# 28DIP.net
KiCad netlist of a schematic drawn in EAGLE
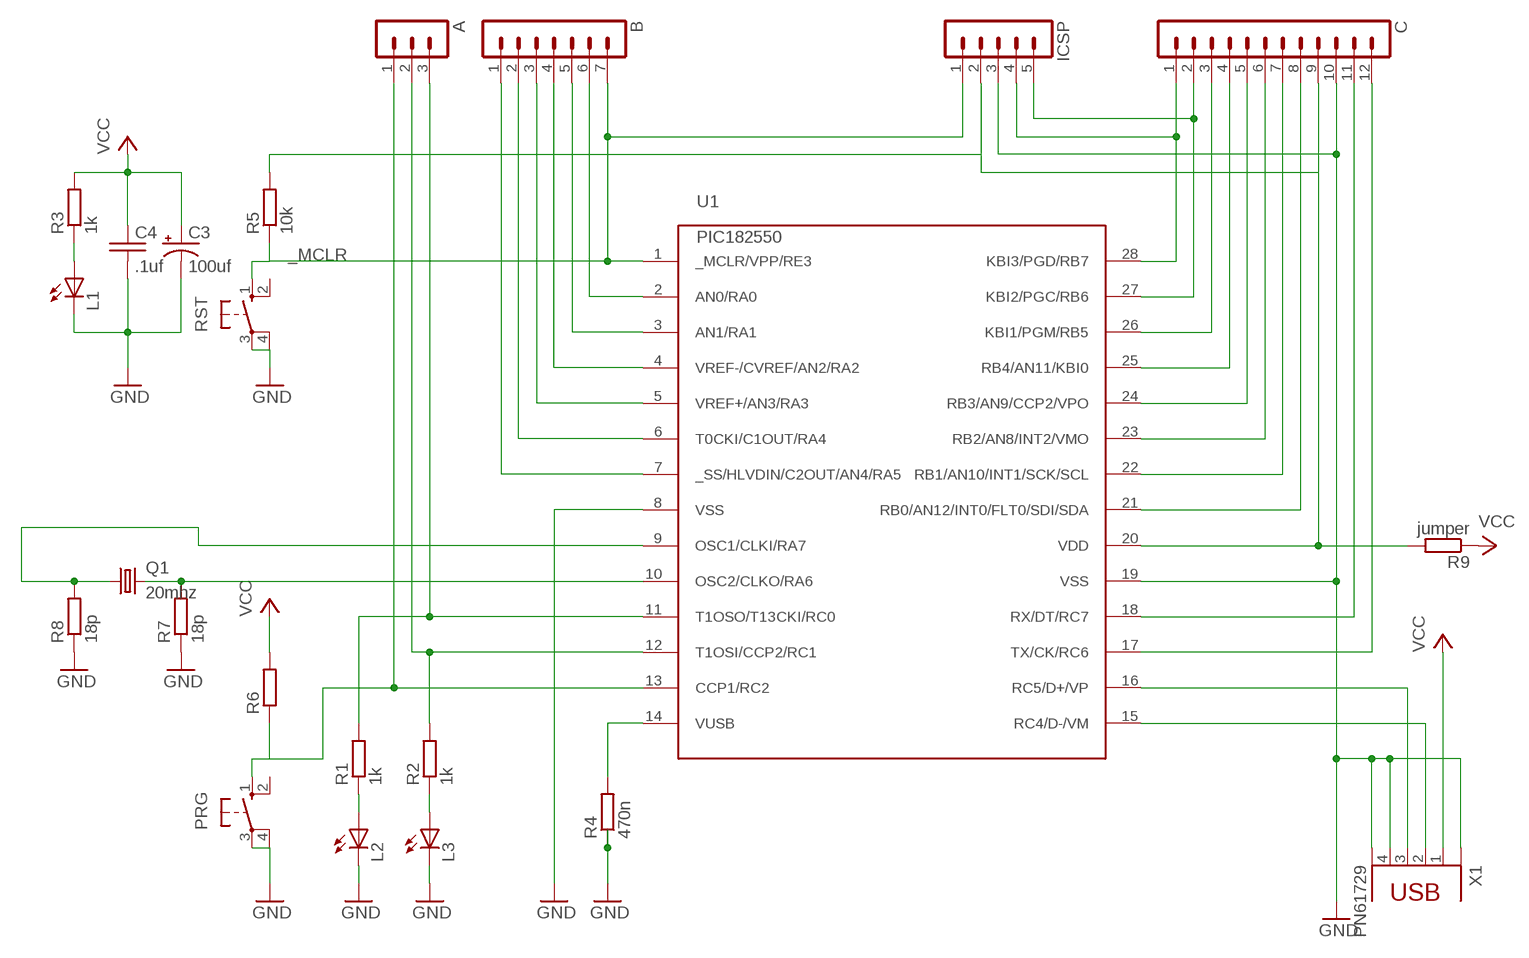
[diagram p0: schematic, sheet 1]

(export (version "E")
  (design (tool "Eeschema 10.0.6"))
  (components
    (comp (ref "A")
      (value "MA03-1")
      (footprint "eagle-import:MA03-1")
      (libsource (lib "eagle-import") (part "MA03-1"))
    )
    (comp (ref "B")
      (value "MA07-1")
      (footprint "eagle-import:MA07-1")
      (libsource (lib "eagle-import") (part "MA07-1"))
    )
    (comp (ref "C")
      (value "MA12-1")
      (footprint "eagle-import:MA12-1")
      (libsource (lib "eagle-import") (part "MA12-1"))
    )
    (comp (ref "C3")
      (value "100uf")
      (footprint "eagle-import:CAP_0200ELECTROLYTIC_0250")
      (libsource (lib "eagle-import") (part "CAP_ELECTROLYTICCAP_0200ELECTROLYTIC_0250"))
    )
    (comp (ref "C4")
      (value ".1uf")
      (footprint "eagle-import:CAP_0100")
      (libsource (lib "eagle-import") (part "CAPCAP_0100"))
    )
    (comp (ref "ICSP")
      (value "MA05-1")
      (footprint "eagle-import:MA05-1")
      (libsource (lib "eagle-import") (part "MA05-1"))
    )
    (comp (ref "L1")
      (value "LED")
      (footprint "eagle-import:LED5MM")
      (libsource (lib "eagle-import") (part "LED"))
    )
    (comp (ref "L2")
      (value "LED")
      (footprint "eagle-import:LED5MM")
      (libsource (lib "eagle-import") (part "LED"))
    )
    (comp (ref "L3")
      (value "LED")
      (footprint "eagle-import:LED5MM")
      (libsource (lib "eagle-import") (part "LED"))
    )
    (comp (ref "PRG")
      (value "10-XX")
      (footprint "eagle-import:B3F-10XX")
      (fields (field (name "MPN") "B3F-1000"))
      (libsource (lib "eagle-import") (part "10-XX"))
    )
    (comp (ref "Q1")
      (value "20mhz")
      (footprint "eagle-import:HC49_S")
      (libsource (lib "eagle-import") (part "CRYTALHC49S"))
    )
    (comp (ref "R1")
      (value "1k")
      (footprint "eagle-import:M0805")
      (libsource (lib "eagle-import") (part "R-EU_M0805"))
    )
    (comp (ref "R2")
      (value "1k")
      (footprint "eagle-import:M0805")
      (libsource (lib "eagle-import") (part "R-EU_M0805"))
    )
    (comp (ref "R3")
      (value "1k")
      (footprint "eagle-import:M0805")
      (libsource (lib "eagle-import") (part "R-EU_M0805"))
    )
    (comp (ref "R4")
      (value "470n")
      (footprint "eagle-import:M0805")
      (libsource (lib "eagle-import") (part "R-EU_M0805"))
    )
    (comp (ref "R5")
      (value "10k")
      (footprint "eagle-import:M0805")
      (libsource (lib "eagle-import") (part "R-EU_M0805"))
    )
    (comp (ref "R6")
      (value "R-EU_M0805")
      (footprint "eagle-import:M0805")
      (libsource (lib "eagle-import") (part "R-EU_M0805"))
    )
    (comp (ref "R7")
      (value "18p")
      (footprint "eagle-import:M0805")
      (libsource (lib "eagle-import") (part "R-EU_M0805"))
    )
    (comp (ref "R8")
      (value "18p")
      (footprint "eagle-import:M0805")
      (libsource (lib "eagle-import") (part "R-EU_M0805"))
    )
    (comp (ref "R9")
      (value "jumper")
      (footprint "eagle-import:M1206")
      (libsource (lib "eagle-import") (part "R-EU_M1206"))
    )
    (comp (ref "RST")
      (value "10-XX")
      (footprint "eagle-import:B3F-10XX")
      (fields (field (name "MPN") "B3F-1000"))
      (libsource (lib "eagle-import") (part "10-XX"))
    )
    (comp (ref "U1")
      (value "PIC182550")
      (footprint "eagle-import:DIL28-3")
      (libsource (lib "eagle-import") (part "PIC182455"))
    )
    (comp (ref "X1")
      (value "PN61729")
      (footprint "eagle-import:PN61729")
      (libsource (lib "eagle-import") (part "PN61729"))
    )
  )
  (nets
    (net (code "1") (name "/_MCLR") (class "Default")
      (node (ref "B") (pin "7") (pinfunction "7_7") (pintype "passive"))
      (node (ref "ICSP") (pin "1") (pinfunction "1_1") (pintype "passive"))
      (node (ref "R5") (pin "1") (pinfunction "1_1") (pintype "passive"))
      (node (ref "RST") (pin "1") (pinfunction "S_1") (pintype "passive"))
      (node (ref "U1") (pin "1") (pinfunction "_MCLR/VPP/RE3_1") (pintype "input"))
    )
    (net (code "2") (name "GND") (class "Default")
      (node (ref "C") (pin "10") (pinfunction "10_10") (pintype "passive"))
      (node (ref "C3") (pin "-") (pinfunction "-_-") (pintype "passive"))
      (node (ref "C4") (pin "2") (pinfunction "2_2") (pintype "passive"))
      (node (ref "ICSP") (pin "3") (pinfunction "3_3") (pintype "passive"))
      (node (ref "L1") (pin "K") (pinfunction "C_K") (pintype "passive"))
      (node (ref "L2") (pin "K") (pinfunction "C_K") (pintype "passive"))
      (node (ref "L3") (pin "K") (pinfunction "C_K") (pintype "passive"))
      (node (ref "PRG") (pin "3") (pinfunction "P_3") (pintype "passive"))
      (node (ref "PRG") (pin "4") (pinfunction "P1_4") (pintype "passive"))
      (node (ref "R4") (pin "1") (pinfunction "1_1") (pintype "passive"))
      (node (ref "R7") (pin "1") (pinfunction "1_1") (pintype "passive"))
      (node (ref "R8") (pin "1") (pinfunction "1_1") (pintype "passive"))
      (node (ref "RST") (pin "3") (pinfunction "P_3") (pintype "passive"))
      (node (ref "RST") (pin "4") (pinfunction "P1_4") (pintype "passive"))
      (node (ref "U1") (pin "19") (pinfunction "VSS_19") (pintype "power_in"))
      (node (ref "U1") (pin "8") (pinfunction "VSS_8") (pintype "power_in"))
      (node (ref "X1") (pin "4") (pinfunction "4_4") (pintype "bidirectional"))
      (node (ref "X1") (pin "GND1") (pinfunction "G1_GND1") (pintype "power_in"))
      (node (ref "X1") (pin "GND2") (pinfunction "G2_GND2") (pintype "power_in"))
    )
    (net (code "3") (name "Net-(L1-PadA)") (class "Default")
      (node (ref "L1") (pin "A") (pinfunction "A_A") (pintype "passive"))
      (node (ref "R3") (pin "1") (pinfunction "1_1") (pintype "passive"))
    )
    (net (code "4") (name "Net-(L2-PadA)") (class "Default")
      (node (ref "L2") (pin "A") (pinfunction "A_A") (pintype "passive"))
      (node (ref "R1") (pin "1") (pinfunction "1_1") (pintype "passive"))
    )
    (net (code "5") (name "Net-(L3-PadA)") (class "Default")
      (node (ref "L3") (pin "A") (pinfunction "A_A") (pintype "passive"))
      (node (ref "R2") (pin "1") (pinfunction "1_1") (pintype "passive"))
    )
    (net (code "6") (name "Net-(PRG-S)") (class "Default")
      (node (ref "A") (pin "1") (pinfunction "1_1") (pintype "passive"))
      (node (ref "PRG") (pin "1") (pinfunction "S_1") (pintype "passive"))
      (node (ref "R6") (pin "1") (pinfunction "1_1") (pintype "passive"))
      (node (ref "U1") (pin "13") (pinfunction "CCP1/RC2_13") (pintype "bidirectional"))
    )
    (net (code "7") (name "Net-(U1-AN0{slash}RA0)") (class "Default")
      (node (ref "B") (pin "6") (pinfunction "6_6") (pintype "passive"))
      (node (ref "U1") (pin "2") (pinfunction "AN0/RA0_2") (pintype "bidirectional"))
    )
    (net (code "8") (name "Net-(U1-AN1{slash}RA1)") (class "Default")
      (node (ref "B") (pin "5") (pinfunction "5_5") (pintype "passive"))
      (node (ref "U1") (pin "3") (pinfunction "AN1/RA1_3") (pintype "bidirectional"))
    )
    (net (code "9") (name "Net-(U1-KBI1{slash}PGM{slash}RB5)") (class "Default")
      (node (ref "C") (pin "3") (pinfunction "3_3") (pintype "passive"))
      (node (ref "U1") (pin "26") (pinfunction "KBI1/PGM/RB5_26") (pintype "bidirectional"))
    )
    (net (code "10") (name "Net-(U1-KBI2{slash}PGC{slash}RB6)") (class "Default")
      (node (ref "C") (pin "2") (pinfunction "2_2") (pintype "passive"))
      (node (ref "ICSP") (pin "5") (pinfunction "5_5") (pintype "passive"))
      (node (ref "U1") (pin "27") (pinfunction "KBI2/PGC/RB6_27") (pintype "bidirectional"))
    )
    (net (code "11") (name "Net-(U1-KBI3{slash}PGD{slash}RB7)") (class "Default")
      (node (ref "C") (pin "1") (pinfunction "1_1") (pintype "passive"))
      (node (ref "ICSP") (pin "4") (pinfunction "4_4") (pintype "passive"))
      (node (ref "U1") (pin "28") (pinfunction "KBI3/PGD/RB7_28") (pintype "bidirectional"))
    )
    (net (code "12") (name "Net-(U1-OSC1{slash}CLKI{slash}RA7)") (class "Default")
      (node (ref "Q1") (pin "1") (pinfunction "1_1") (pintype "passive"))
      (node (ref "R8") (pin "2") (pinfunction "2_2") (pintype "passive"))
      (node (ref "U1") (pin "9") (pinfunction "OSC1/CLKI/RA7_9") (pintype "bidirectional"))
    )
    (net (code "13") (name "Net-(U1-OSC2{slash}CLKO{slash}RA6)") (class "Default")
      (node (ref "Q1") (pin "2") (pinfunction "2_2") (pintype "passive"))
      (node (ref "R7") (pin "2") (pinfunction "2_2") (pintype "passive"))
      (node (ref "U1") (pin "10") (pinfunction "OSC2/CLKO/RA6_10") (pintype "bidirectional"))
    )
    (net (code "14") (name "Net-(U1-RB0{slash}AN12{slash}INT0{slash}FLT0{slash}SDI{slash}SDA)") (class "Default")
      (node (ref "C") (pin "8") (pinfunction "8_8") (pintype "passive"))
      (node (ref "U1") (pin "21") (pinfunction "RB0/AN12/INT0/FLT0/SDI/SDA_21") (pintype "bidirectional"))
    )
    (net (code "15") (name "Net-(U1-RB1{slash}AN10{slash}INT1{slash}SCK{slash}SCL)") (class "Default")
      (node (ref "C") (pin "7") (pinfunction "7_7") (pintype "passive"))
      (node (ref "U1") (pin "22") (pinfunction "RB1/AN10/INT1/SCK/SCL_22") (pintype "bidirectional"))
    )
    (net (code "16") (name "Net-(U1-RB2{slash}AN8{slash}INT2{slash}VMO)") (class "Default")
      (node (ref "C") (pin "6") (pinfunction "6_6") (pintype "passive"))
      (node (ref "U1") (pin "23") (pinfunction "RB2/AN8/INT2/VMO_23") (pintype "bidirectional"))
    )
    (net (code "17") (name "Net-(U1-RB3{slash}AN9{slash}CCP2{slash}VPO)") (class "Default")
      (node (ref "C") (pin "5") (pinfunction "5_5") (pintype "passive"))
      (node (ref "U1") (pin "24") (pinfunction "RB3/AN9/CCP2/VPO_24") (pintype "bidirectional"))
    )
    (net (code "18") (name "Net-(U1-RB4{slash}AN11{slash}KBI0)") (class "Default")
      (node (ref "C") (pin "4") (pinfunction "4_4") (pintype "passive"))
      (node (ref "U1") (pin "25") (pinfunction "RB4/AN11/KBI0_25") (pintype "bidirectional"))
    )
    (net (code "19") (name "Net-(U1-RC4{slash}D-{slash}VM)") (class "Default")
      (node (ref "U1") (pin "15") (pinfunction "RC4/D-/VM_15") (pintype "bidirectional"))
      (node (ref "X1") (pin "2") (pinfunction "2_2") (pintype "bidirectional"))
    )
    (net (code "20") (name "Net-(U1-RC5{slash}D+{slash}VP)") (class "Default")
      (node (ref "U1") (pin "16") (pinfunction "RC5/D+/VP_16") (pintype "bidirectional"))
      (node (ref "X1") (pin "3") (pinfunction "3_3") (pintype "bidirectional"))
    )
    (net (code "21") (name "Net-(U1-RX{slash}DT{slash}RC7)") (class "Default")
      (node (ref "C") (pin "11") (pinfunction "11_11") (pintype "passive"))
      (node (ref "U1") (pin "18") (pinfunction "RX/DT/RC7_18") (pintype "bidirectional"))
    )
    (net (code "22") (name "Net-(U1-T0CKI{slash}C1OUT{slash}RA4)") (class "Default")
      (node (ref "B") (pin "2") (pinfunction "2_2") (pintype "passive"))
      (node (ref "U1") (pin "6") (pinfunction "T0CKI/C1OUT/RA4_6") (pintype "bidirectional"))
    )
    (net (code "23") (name "Net-(U1-T1OSI{slash}CCP2{slash}RC1)") (class "Default")
      (node (ref "A") (pin "2") (pinfunction "2_2") (pintype "passive"))
      (node (ref "R2") (pin "2") (pinfunction "2_2") (pintype "passive"))
      (node (ref "U1") (pin "12") (pinfunction "T1OSI/CCP2/RC1_12") (pintype "bidirectional"))
    )
    (net (code "24") (name "Net-(U1-T1OSO{slash}T13CKI{slash}RC0)") (class "Default")
      (node (ref "A") (pin "3") (pinfunction "3_3") (pintype "passive"))
      (node (ref "R1") (pin "2") (pinfunction "2_2") (pintype "passive"))
      (node (ref "U1") (pin "11") (pinfunction "T1OSO/T13CKI/RC0_11") (pintype "bidirectional"))
    )
    (net (code "25") (name "Net-(U1-TX{slash}CK{slash}RC6)") (class "Default")
      (node (ref "C") (pin "12") (pinfunction "12_12") (pintype "passive"))
      (node (ref "U1") (pin "17") (pinfunction "TX/CK/RC6_17") (pintype "bidirectional"))
    )
    (net (code "26") (name "Net-(U1-VDD)") (class "Default")
      (node (ref "C") (pin "9") (pinfunction "9_9") (pintype "passive"))
      (node (ref "ICSP") (pin "2") (pinfunction "2_2") (pintype "passive"))
      (node (ref "R5") (pin "2") (pinfunction "2_2") (pintype "passive"))
      (node (ref "R9") (pin "2") (pinfunction "2_2") (pintype "passive"))
      (node (ref "U1") (pin "20") (pinfunction "VDD_20") (pintype "power_in"))
    )
    (net (code "27") (name "Net-(U1-VREF+{slash}AN3{slash}RA3)") (class "Default")
      (node (ref "B") (pin "3") (pinfunction "3_3") (pintype "passive"))
      (node (ref "U1") (pin "5") (pinfunction "VREF+/AN3/RA3_5") (pintype "bidirectional"))
    )
    (net (code "28") (name "Net-(U1-VREF-{slash}CVREF{slash}AN2{slash}RA2)") (class "Default")
      (node (ref "B") (pin "4") (pinfunction "4_4") (pintype "passive"))
      (node (ref "U1") (pin "4") (pinfunction "VREF-/CVREF/AN2/RA2_4") (pintype "bidirectional"))
    )
    (net (code "29") (name "Net-(U1-VUSB)") (class "Default")
      (node (ref "R4") (pin "2") (pinfunction "2_2") (pintype "passive"))
      (node (ref "U1") (pin "14") (pinfunction "VUSB_14") (pintype "bidirectional"))
    )
    (net (code "30") (name "Net-(U1-_SS{slash}HLVDIN{slash}C2OUT{slash}AN4{slash}RA5)") (class "Default")
      (node (ref "B") (pin "1") (pinfunction "1_1") (pintype "passive"))
      (node (ref "U1") (pin "7") (pinfunction "_SS/HLVDIN/C2OUT/AN4/RA5_7") (pintype "bidirectional"))
    )
    (net (code "31") (name "VCC") (class "Default")
      (node (ref "C3") (pin "+") (pinfunction "+_+") (pintype "passive"))
      (node (ref "C4") (pin "1") (pinfunction "1_1") (pintype "passive"))
      (node (ref "R3") (pin "2") (pinfunction "2_2") (pintype "passive"))
      (node (ref "R6") (pin "2") (pinfunction "2_2") (pintype "passive"))
      (node (ref "R9") (pin "1") (pinfunction "1_1") (pintype "passive"))
      (node (ref "X1") (pin "1") (pinfunction "1_1") (pintype "bidirectional"))
    )
    (net (code "32") (name "unconnected-(PRG-S1-Pad2)") (class "Default")
      (node (ref "PRG") (pin "2") (pinfunction "S1_2") (pintype "passive"))
    )
    (net (code "33") (name "unconnected-(RST-S1-Pad2)") (class "Default")
      (node (ref "RST") (pin "2") (pinfunction "S1_2") (pintype "passive"))
    )
  )
)
